# US_EPS_MCU.net
KiCad netlist of a schematic drawn in Altium Designer
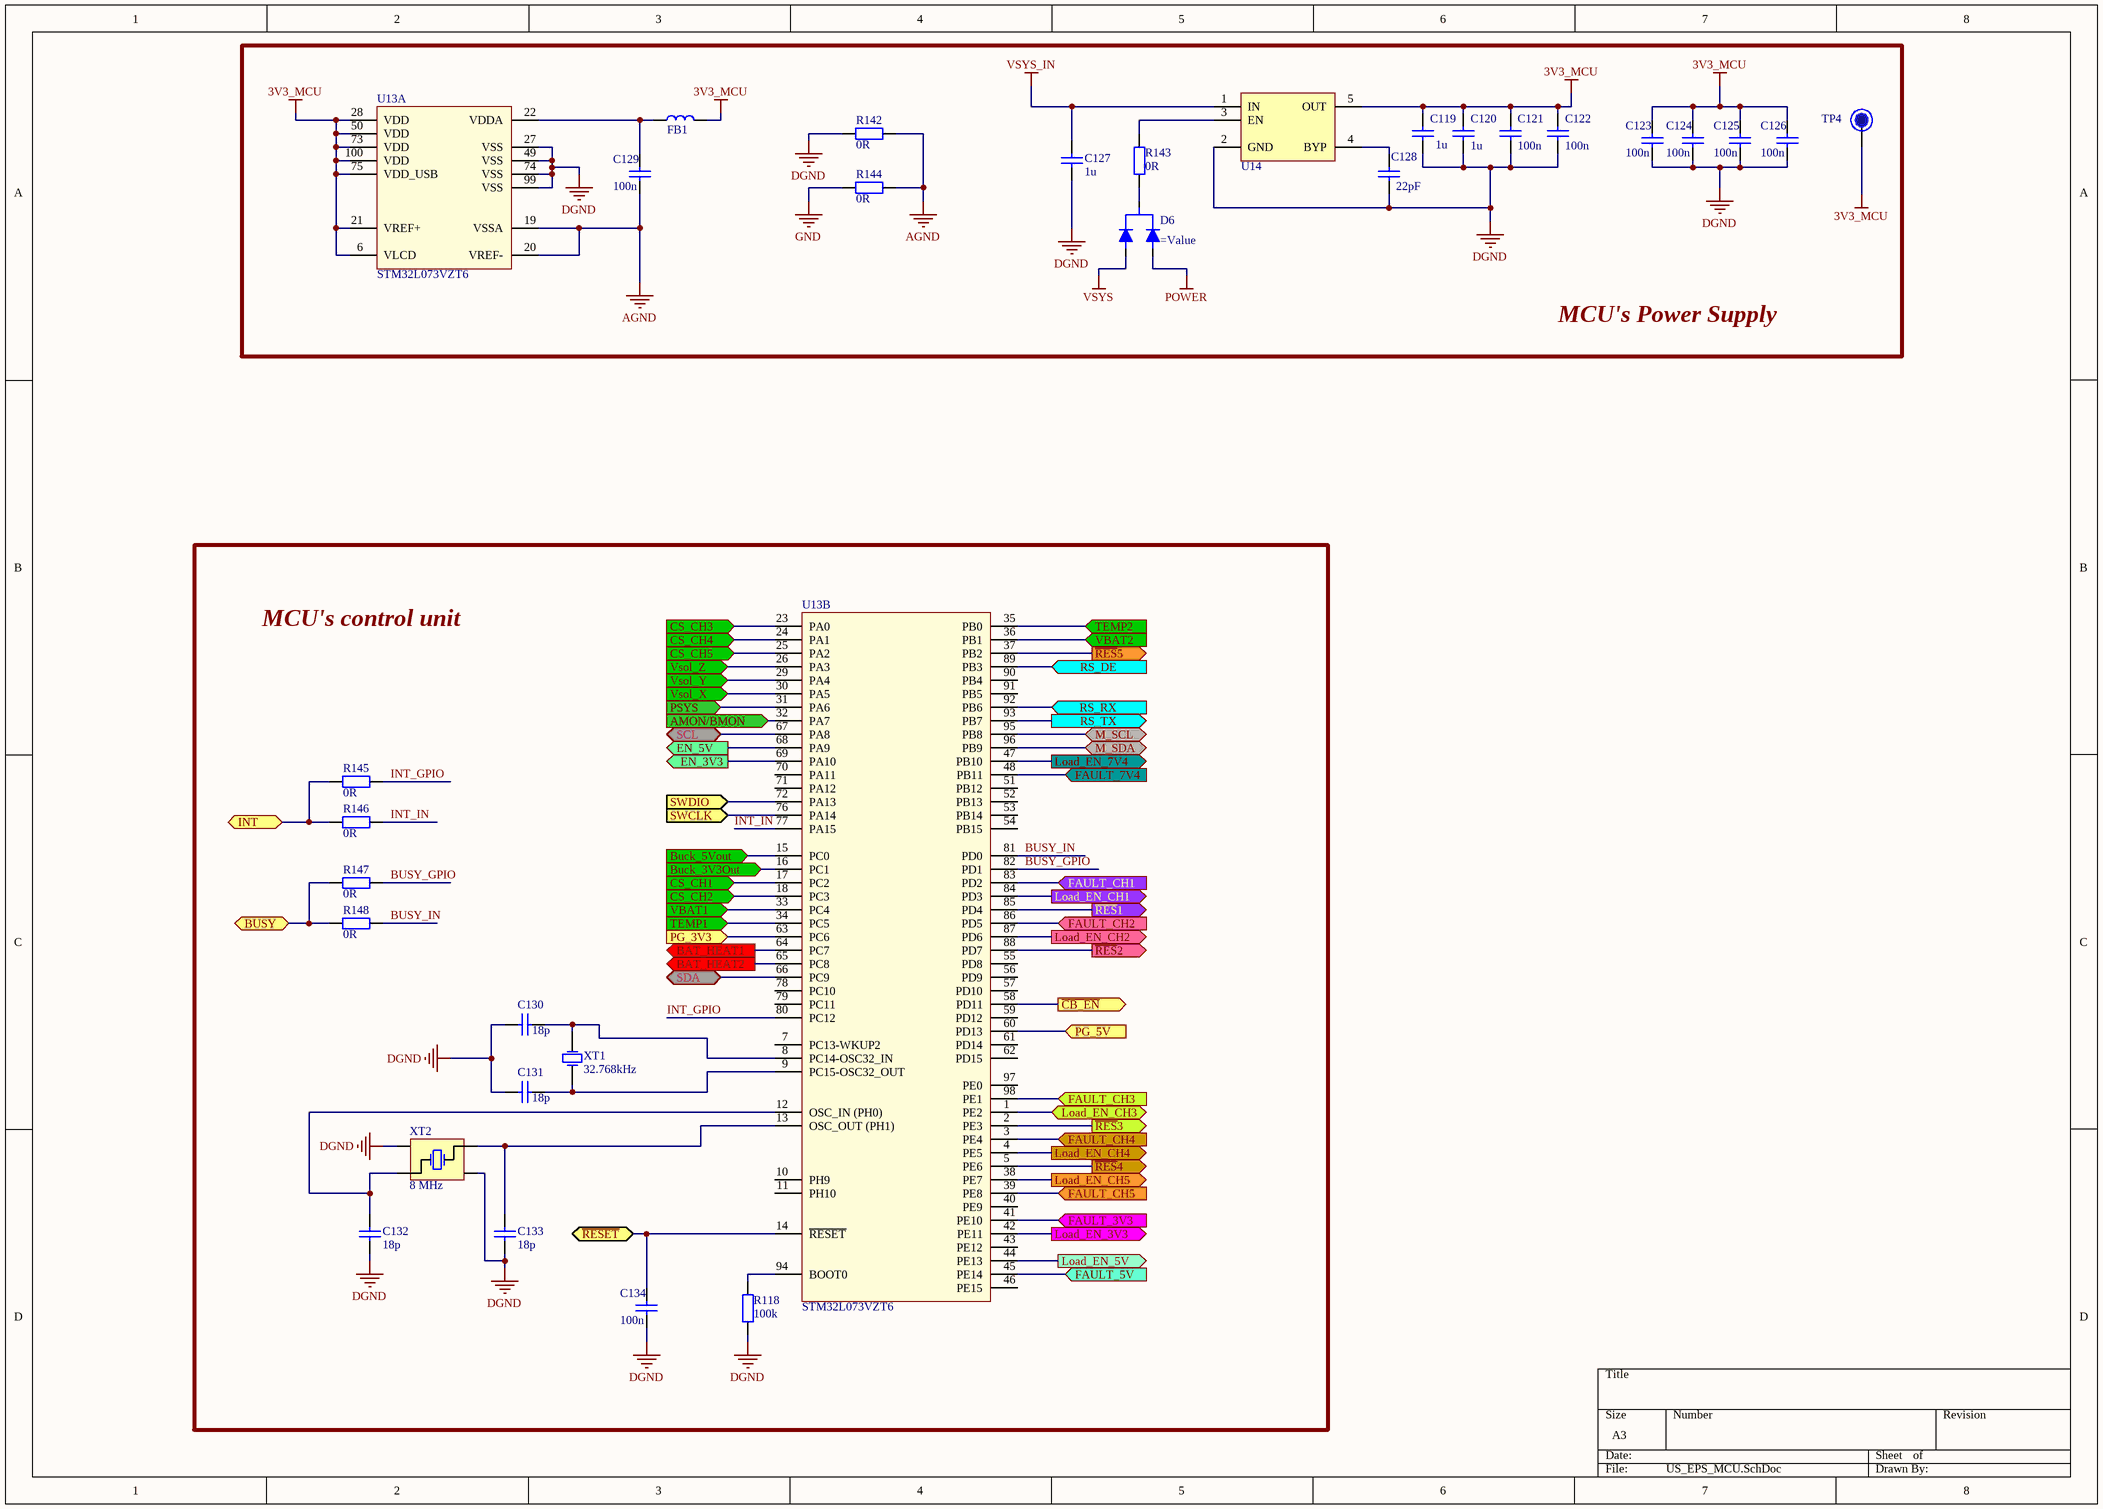
[diagram p0: US_EPS_MCU.SchDoc]

(export (version "E")
  (design (tool "Eeschema 10.0.6"))
  (components
    (comp (ref "C119")
      (value "1u")
      (footprint "C0603_IPC_HD")
      (description "CAP CER 1UF 16V X7R 0603")
      (fields
        (field (name "MANUFACTURER") "Samsung Electro-Mechanics")
        (field (name "MANUFACTURER PART NUMBER") "CL10B105MO8NNWC")
      )
      (libsource (lib "alfasat_lib") (part "CL10B105MO8NNWC"))
    )
    (comp (ref "C120")
      (value "1u")
      (footprint "C0603_IPC_HD")
      (description "CAP CER 1UF 16V X7R 0603")
      (fields
        (field (name "MANUFACTURER") "Samsung Electro-Mechanics")
        (field (name "MANUFACTURER PART NUMBER") "CL10B105MO8NNWC")
      )
      (libsource (lib "alfasat_lib") (part "CL10B105MO8NNWC"))
    )
    (comp (ref "C121")
      (value "100n")
      (footprint "C0603_IPC_HD")
      (description "CAP CER 0.1UF 16V X7R 0603")
      (fields
        (field (name "MANUFACTURER") "Samsung Electro-Mechanics")
        (field (name "MANUFACTURER PART NUMBER") "CL10B104KO8NNNC")
      )
      (libsource (lib "alfasat_lib") (part "CL10B104KO8NNNC"))
    )
    (comp (ref "C122")
      (value "100n")
      (footprint "C0603_IPC_HD")
      (description "CAP CER 0.1UF 16V X7R 0603")
      (fields
        (field (name "MANUFACTURER") "Samsung Electro-Mechanics")
        (field (name "MANUFACTURER PART NUMBER") "CL10B104KO8NNNC")
      )
      (libsource (lib "alfasat_lib") (part "CL10B104KO8NNNC"))
    )
    (comp (ref "C123")
      (value "100n")
      (footprint "C0603_IPC_HD")
      (description "CAP CER 0.1UF 16V X7R 0603")
      (fields
        (field (name "MANUFACTURER") "Samsung Electro-Mechanics")
        (field (name "MANUFACTURER PART NUMBER") "CL10B104KO8NNNC")
      )
      (libsource (lib "alfasat_lib") (part "CL10B104KO8NNNC"))
    )
    (comp (ref "C124")
      (value "100n")
      (footprint "C0603_IPC_HD")
      (description "CAP CER 0.1UF 16V X7R 0603")
      (fields
        (field (name "MANUFACTURER") "Samsung Electro-Mechanics")
        (field (name "MANUFACTURER PART NUMBER") "CL10B104KO8NNNC")
      )
      (libsource (lib "alfasat_lib") (part "CL10B104KO8NNNC"))
    )
    (comp (ref "C125")
      (value "100n")
      (footprint "C0603_IPC_HD")
      (description "CAP CER 0.1UF 16V X7R 0603")
      (fields
        (field (name "MANUFACTURER") "Samsung Electro-Mechanics")
        (field (name "MANUFACTURER PART NUMBER") "CL10B104KO8NNNC")
      )
      (libsource (lib "alfasat_lib") (part "CL10B104KO8NNNC"))
    )
    (comp (ref "C126")
      (value "100n")
      (footprint "C0603_IPC_HD")
      (description "CAP CER 0.1UF 16V X7R 0603")
      (fields
        (field (name "MANUFACTURER") "Samsung Electro-Mechanics")
        (field (name "MANUFACTURER PART NUMBER") "CL10B104KO8NNNC")
      )
      (libsource (lib "alfasat_lib") (part "CL10B104KO8NNNC"))
    )
    (comp (ref "C127")
      (value "1u")
      (footprint "C0603_IPC_HD")
      (description "CAP CER 1UF 16V X7R 0603")
      (fields
        (field (name "MANUFACTURER") "Samsung Electro-Mechanics")
        (field (name "MANUFACTURER PART NUMBER") "CL10B105MO8NNWC")
      )
      (libsource (lib "alfasat_lib") (part "CL10B105MO8NNWC"))
    )
    (comp (ref "C128")
      (value "22pF")
      (footprint "C0603_IPC_HD")
      (description "CAP CER 22PF 50V C0G/NP0 0603")
      (fields
        (field (name "MANUFACTURER") "Wurth Electronics Inc.")
        (field (name "MANUFACTURER PART NUMBER") "885012006053")
      )
      (libsource (lib "alfasat_lib_eps") (part "CL0603_22pF_50V"))
    )
    (comp (ref "C129")
      (value "100n")
      (footprint "C0603_IPC_HD")
      (description "CAP CER 0.1UF 16V X7R 0603")
      (fields
        (field (name "MANUFACTURER") "Samsung Electro-Mechanics")
        (field (name "MANUFACTURER PART NUMBER") "CL10B104KO8NNNC")
      )
      (libsource (lib "alfasat_lib") (part "CL10B104KO8NNNC"))
    )
    (comp (ref "C130")
      (value "18p")
      (footprint "C0603_IPC_HD")
      (description "CAP CER 18PF 50V C0G/NP0 0603")
      (fields
        (field (name "MANUFACTURER") "Samsung Electro-Mechanics")
        (field (name "MANUFACTURER PART NUMBER") "CL10C180JB8NNNC")
      )
      (libsource (lib "alfasat_lib") (part "CL10C180JB8NNNC"))
    )
    (comp (ref "C131")
      (value "18p")
      (footprint "C0603_IPC_HD")
      (description "CAP CER 18PF 50V C0G/NP0 0603")
      (fields
        (field (name "MANUFACTURER") "Samsung Electro-Mechanics")
        (field (name "MANUFACTURER PART NUMBER") "CL10C180JB8NNNC")
      )
      (libsource (lib "alfasat_lib") (part "CL10C180JB8NNNC"))
    )
    (comp (ref "C132")
      (value "18p")
      (footprint "C0603_IPC_HD")
      (description "CAP CER 18PF 50V C0G/NP0 0603")
      (fields
        (field (name "MANUFACTURER") "Samsung Electro-Mechanics")
        (field (name "MANUFACTURER PART NUMBER") "CL10C180JB8NNNC")
      )
      (libsource (lib "alfasat_lib") (part "CL10C180JB8NNNC"))
    )
    (comp (ref "C133")
      (value "18p")
      (footprint "C0603_IPC_HD")
      (description "CAP CER 18PF 50V C0G/NP0 0603")
      (fields
        (field (name "MANUFACTURER") "Samsung Electro-Mechanics")
        (field (name "MANUFACTURER PART NUMBER") "CL10C180JB8NNNC")
      )
      (libsource (lib "alfasat_lib") (part "CL10C180JB8NNNC"))
    )
    (comp (ref "C134")
      (value "100n")
      (footprint "C0603_IPC_HD")
      (description "CAP CER 0.1UF 16V X7R 0603")
      (fields
        (field (name "MANUFACTURER") "Samsung Electro-Mechanics")
        (field (name "MANUFACTURER PART NUMBER") "CL10B104KO8NNNC")
      )
      (libsource (lib "alfasat_lib") (part "CL10B104KO8NNNC"))
    )
    (comp (ref "D6")
      (value "~")
      (footprint "BAT54C_SOT23")
      (description "Diode Schottky 30V 200mA Surface Mount SOT-23(ISL9237)")
      (fields
        (field (name "MANUFACTURER") "Diodes Incorporated")
        (field (name "MANUFACTURER PART NUMBER") "BAT54CQ-7-F")
      )
      (libsource (lib "alfasat_lib_eps") (part "BAT54CQ-7"))
    )
    (comp (ref "FB1")
      (value "MH1608-601Y")
      (footprint "L0603_IPC_MD")
      (description "FERRITE BEAD 600R@100MHz 0603 for Power Line, 1000mA")
      (fields (field (name "MANUFACTURER") "Bourns Inc."))
      (libsource (lib "alfasat_lib") (part "MH1608-601Y"))
    )
    (comp (ref "R118")
      (value "100k")
      (footprint "R0603_IPC_MD")
      (description "RES 100K OHM 1% 1/10W 0603")
      (fields
        (field (name "MANUFACTURER") "Stackpole Electronics Inc")
        (field (name "MANUFACTURER PART NUMBER") "RMCF0603FT100K")
      )
      (libsource (lib "alfasat_lib_eps") (part "CR0603-JW-104ELF"))
    )
    (comp (ref "R142")
      (value "0R")
      (footprint "R0603_IPC_MD")
      (description "RES SMD 0 OHM JUMPER 1/10W 0603")
      (fields
        (field (name "MANUFACTURER") "Bourns Inc.")
        (field (name "MANUFACTURER PART NUMBER") "CR0603-J/-000ELF")
      )
      (libsource (lib "alfasat_lib") (part "CR0603-J/-000ELF"))
    )
    (comp (ref "R143")
      (value "0R")
      (footprint "R0603_IPC_MD")
      (description "RES SMD 0 OHM JUMPER 1/10W 0603")
      (fields
        (field (name "MANUFACTURER") "Bourns Inc.")
        (field (name "MANUFACTURER PART NUMBER") "CR0603-J/-000ELF")
      )
      (libsource (lib "") (part "CR0603-J/-000ELF_1"))
    )
    (comp (ref "R144")
      (value "0R")
      (footprint "R0603_IPC_MD")
      (description "RES SMD 0 OHM JUMPER 1/10W 0603")
      (fields
        (field (name "MANUFACTURER") "Bourns Inc.")
        (field (name "MANUFACTURER PART NUMBER") "CR0603-J/-000ELF")
      )
      (libsource (lib "alfasat_lib") (part "CR0603-J/-000ELF"))
    )
    (comp (ref "R145")
      (value "0R")
      (footprint "R0603_IPC_MD")
      (description "RES SMD 0 OHM JUMPER 1/10W 0603")
      (fields
        (field (name "MANUFACTURER") "Bourns Inc.")
        (field (name "MANUFACTURER PART NUMBER") "CR0603-J/-000ELF")
      )
      (libsource (lib "alfasat_lib") (part "CR0603-J/-000ELF"))
    )
    (comp (ref "R146")
      (value "0R")
      (footprint "R0603_IPC_MD")
      (description "RES SMD 0 OHM JUMPER 1/10W 0603")
      (fields
        (field (name "MANUFACTURER") "Bourns Inc.")
        (field (name "MANUFACTURER PART NUMBER") "CR0603-J/-000ELF")
      )
      (libsource (lib "alfasat_lib") (part "CR0603-J/-000ELF"))
    )
    (comp (ref "R147")
      (value "0R")
      (footprint "R0603_IPC_MD")
      (description "RES SMD 0 OHM JUMPER 1/10W 0603")
      (fields
        (field (name "MANUFACTURER") "Bourns Inc.")
        (field (name "MANUFACTURER PART NUMBER") "CR0603-J/-000ELF")
      )
      (libsource (lib "alfasat_lib") (part "CR0603-J/-000ELF"))
    )
    (comp (ref "R148")
      (value "0R")
      (footprint "R0603_IPC_MD")
      (description "RES SMD 0 OHM JUMPER 1/10W 0603")
      (fields
        (field (name "MANUFACTURER") "Bourns Inc.")
        (field (name "MANUFACTURER PART NUMBER") "CR0603-J/-000ELF")
      )
      (libsource (lib "alfasat_lib") (part "CR0603-J/-000ELF"))
    )
    (comp (ref "TP4")
      (value "Test Point")
      (footprint "TestPoint_1M5")
      (libsource (lib "alfasat_lib") (part "TP"))
    )
    (comp (ref "U13")
      (value "STM32L073VZT6")
      (footprint "STM32L073_TSQFP50P1600X1600X160-100N")
      (description "ARM® Cortex®-M0+ STM32L0 Microcontroller IC 32-Bit 32MHz 192KB (192K x 8) FLASH 100-LQFP (14x14)")
      (fields (field (name "MANUFACTURER") "STMicroelectronics"))
      (libsource (lib "alfasat_lib_eps") (part "STM32L073VZT6_EPS"))
    )
    (comp (ref "U14")
      (value "MIC5216-3.3YM5-TR")
      (footprint "SOT23-5_(MT)")
      (description "IC REG LINEAR 3.3V 500MA SOT23-5")
      (fields (field (name "MANUFACTURER") "Microchip Technology"))
      (libsource (lib "alfasat_lib_eps") (part "MIC5216-3.3YM5-TR"))
    )
    (comp (ref "XT1")
      (value "32.768kHz")
      (footprint "FC-135R")
      (description "32.768kHz ±20ppm Crystal 12.5pF 70 kOhms 2-SMD, No Lead")
      (fields
        (field (name "MANUFACTURER") "EPSON")
        (field (name "MANUFACTURER PART NUMBER") "FC-135 32.7680KA-A5")
      )
      (libsource (lib "alfasat_lib_eps") (part "FC-135-32.7680K"))
    )
    (comp (ref "XT2")
      (value "8 MHz")
      (footprint "5.0X3.2_4PAD_SMT")
      (description "8MHz ±10ppm Crystal 10pF 200 Ohms 4-SMD, No Lead")
      (fields
        (field (name "MANUFACTURER PART NUMBER") "ABM3B-8.000MHZ-10-1-U-T")
        (field (name "MANUFACTURER") "Abracon LLC")
      )
      (libsource (lib "alfasat_lib") (part "ABM3B-8.000MHZ-10-1-U-T"))
    )
  )
  (nets
    (net (code "1") (name "/AMON{slash}BMON") (class "Default")
      (node (ref "U13") (pin "32") (pinfunction "PA7_32") (pintype "passive"))
    )
    (net (code "2") (name "/BAT_HEAT1") (class "Default")
      (node (ref "U13") (pin "64") (pinfunction "PC7_64") (pintype "passive"))
    )
    (net (code "3") (name "/BAT_HEAT2") (class "Default")
      (node (ref "U13") (pin "65") (pinfunction "PC8_65") (pintype "passive"))
    )
    (net (code "4") (name "/BUSY") (class "Default")
      (node (ref "R147") (pin "2") (pinfunction "2_2") (pintype "passive"))
      (node (ref "R148") (pin "2") (pinfunction "2_2") (pintype "passive"))
    )
    (net (code "5") (name "/BUSY_GPIO") (class "Default")
      (node (ref "R147") (pin "1") (pinfunction "1_1") (pintype "passive"))
      (node (ref "U13") (pin "82") (pinfunction "PD1_82") (pintype "passive"))
    )
    (net (code "6") (name "/BUSY_IN") (class "Default")
      (node (ref "R148") (pin "1") (pinfunction "1_1") (pintype "passive"))
      (node (ref "U13") (pin "81") (pinfunction "PD0_81") (pintype "passive"))
    )
    (net (code "7") (name "/Buck_3V3Out") (class "Default")
      (node (ref "U13") (pin "16") (pinfunction "PC1_16") (pintype "passive"))
    )
    (net (code "8") (name "/Buck_5Vout") (class "Default")
      (node (ref "U13") (pin "15") (pinfunction "PC0_15") (pintype "passive"))
    )
    (net (code "9") (name "/CS_CH1") (class "Default")
      (node (ref "U13") (pin "17") (pinfunction "PC2_17") (pintype "passive"))
    )
    (net (code "10") (name "/CS_CH2") (class "Default")
      (node (ref "U13") (pin "18") (pinfunction "PC3_18") (pintype "passive"))
    )
    (net (code "11") (name "/CS_CH3") (class "Default")
      (node (ref "U13") (pin "23") (pinfunction "PA0_23") (pintype "passive"))
    )
    (net (code "12") (name "/CS_CH4") (class "Default")
      (node (ref "U13") (pin "24") (pinfunction "PA1_24") (pintype "passive"))
    )
    (net (code "13") (name "/CS_CH5") (class "Default")
      (node (ref "U13") (pin "25") (pinfunction "PA2_25") (pintype "passive"))
    )
    (net (code "14") (name "/EN_3V3") (class "Default")
      (node (ref "U13") (pin "69") (pinfunction "PA10_69") (pintype "passive"))
    )
    (net (code "15") (name "/EN_5V") (class "Default")
      (node (ref "U13") (pin "68") (pinfunction "PA9_68") (pintype "passive"))
    )
    (net (code "16") (name "/FAULT_3V3") (class "Default")
      (node (ref "U13") (pin "41") (pinfunction "PE10_41") (pintype "passive"))
    )
    (net (code "17") (name "/FAULT_5V") (class "Default")
      (node (ref "U13") (pin "45") (pinfunction "PE14_45") (pintype "passive"))
    )
    (net (code "18") (name "/FAULT_7V4") (class "Default")
      (node (ref "U13") (pin "48") (pinfunction "PB11_48") (pintype "passive"))
    )
    (net (code "19") (name "/FAULT_CH1") (class "Default")
      (node (ref "U13") (pin "83") (pinfunction "PD2_83") (pintype "passive"))
    )
    (net (code "20") (name "/FAULT_CH2") (class "Default")
      (node (ref "U13") (pin "86") (pinfunction "PD5_86") (pintype "passive"))
    )
    (net (code "21") (name "/FAULT_CH3") (class "Default")
      (node (ref "U13") (pin "98") (pinfunction "PE1_98") (pintype "passive"))
    )
    (net (code "22") (name "/FAULT_CH4") (class "Default")
      (node (ref "U13") (pin "3") (pinfunction "PE4_3") (pintype "passive"))
    )
    (net (code "23") (name "/FAULT_CH5") (class "Default")
      (node (ref "U13") (pin "39") (pinfunction "PE8_39") (pintype "passive"))
    )
    (net (code "24") (name "/INT") (class "Default")
      (node (ref "R145") (pin "2") (pinfunction "2_2") (pintype "passive"))
      (node (ref "R146") (pin "2") (pinfunction "2_2") (pintype "passive"))
    )
    (net (code "25") (name "/INT_GPIO") (class "Default")
      (node (ref "R145") (pin "1") (pinfunction "1_1") (pintype "passive"))
      (node (ref "U13") (pin "80") (pinfunction "PC12_80") (pintype "passive"))
    )
    (net (code "26") (name "/INT_IN") (class "Default")
      (node (ref "R146") (pin "1") (pinfunction "1_1") (pintype "passive"))
      (node (ref "U13") (pin "77") (pinfunction "PA15_77") (pintype "passive"))
    )
    (net (code "27") (name "/Load_EN_3V3") (class "Default")
      (node (ref "U13") (pin "42") (pinfunction "PE11_42") (pintype "passive"))
    )
    (net (code "28") (name "/Load_EN_5V") (class "Default")
      (node (ref "U13") (pin "44") (pinfunction "PE13_44") (pintype "passive"))
    )
    (net (code "29") (name "/Load_EN_7V4") (class "Default")
      (node (ref "U13") (pin "47") (pinfunction "PB10_47") (pintype "passive"))
    )
    (net (code "30") (name "/Load_EN_CH1") (class "Default")
      (node (ref "U13") (pin "84") (pinfunction "PD3_84") (pintype "passive"))
    )
    (net (code "31") (name "/Load_EN_CH2") (class "Default")
      (node (ref "U13") (pin "87") (pinfunction "PD6_87") (pintype "passive"))
    )
    (net (code "32") (name "/Load_EN_CH3") (class "Default")
      (node (ref "U13") (pin "1") (pinfunction "PE2_1") (pintype "power_in"))
    )
    (net (code "33") (name "/Load_EN_CH4") (class "Default")
      (node (ref "U13") (pin "4") (pinfunction "PE5_4") (pintype "passive"))
    )
    (net (code "34") (name "/Load_EN_CH5") (class "Default")
      (node (ref "U13") (pin "38") (pinfunction "PE7_38") (pintype "passive"))
    )
    (net (code "35") (name "/M_SCL") (class "Default")
      (node (ref "U13") (pin "95") (pinfunction "PB8_95") (pintype "passive"))
    )
    (net (code "36") (name "/M_SDA") (class "Default")
      (node (ref "U13") (pin "96") (pinfunction "PB9_96") (pintype "passive"))
    )
    (net (code "37") (name "/PG_3V3") (class "Default")
      (node (ref "U13") (pin "63") (pinfunction "PC6_63") (pintype "passive"))
    )
    (net (code "38") (name "/PG_5V") (class "Default")
      (node (ref "U13") (pin "60") (pinfunction "PD13_60") (pintype "passive"))
    )
    (net (code "39") (name "/PSYS") (class "Default")
      (node (ref "U13") (pin "31") (pinfunction "PA6_31") (pintype "passive"))
    )
    (net (code "40") (name "/RS_DE") (class "Default")
      (node (ref "U13") (pin "89") (pinfunction "PB3_89") (pintype "passive"))
    )
    (net (code "41") (name "/RS_RX") (class "Default")
      (node (ref "U13") (pin "92") (pinfunction "PB6_92") (pintype "passive"))
    )
    (net (code "42") (name "/RS_TX") (class "Default")
      (node (ref "U13") (pin "93") (pinfunction "PB7_93") (pintype "passive"))
    )
    (net (code "43") (name "/SCL") (class "Default")
      (node (ref "U13") (pin "67") (pinfunction "PA8_67") (pintype "passive"))
    )
    (net (code "44") (name "/SDA") (class "Default")
      (node (ref "U13") (pin "66") (pinfunction "PC9_66") (pintype "passive"))
    )
    (net (code "45") (name "/SWCLK") (class "Default")
      (node (ref "U13") (pin "76") (pinfunction "PA14_76") (pintype "passive"))
    )
    (net (code "46") (name "/SWDIO") (class "Default")
      (node (ref "U13") (pin "72") (pinfunction "PA13_72") (pintype "passive"))
    )
    (net (code "47") (name "/TEMP1") (class "Default")
      (node (ref "U13") (pin "34") (pinfunction "PC5_34") (pintype "passive"))
    )
    (net (code "48") (name "/TEMP2") (class "Default")
      (node (ref "U13") (pin "35") (pinfunction "PB0_35") (pintype "passive"))
    )
    (net (code "49") (name "/VBAT1") (class "Default")
      (node (ref "U13") (pin "33") (pinfunction "PC4_33") (pintype "passive"))
    )
    (net (code "50") (name "/VBAT2") (class "Default")
      (node (ref "U13") (pin "36") (pinfunction "PB1_36") (pintype "passive"))
    )
    (net (code "51") (name "/Vsol_X") (class "Default")
      (node (ref "U13") (pin "30") (pinfunction "PA5_30") (pintype "passive"))
    )
    (net (code "52") (name "/Vsol_Y") (class "Default")
      (node (ref "U13") (pin "29") (pinfunction "PA4_29") (pintype "passive"))
    )
    (net (code "53") (name "/Vsol_Z") (class "Default")
      (node (ref "U13") (pin "26") (pinfunction "PA3_26") (pintype "passive"))
    )
    (net (code "54") (name "/~{CB_EN}") (class "Default")
      (node (ref "U13") (pin "58") (pinfunction "PD11_58") (pintype "passive"))
    )
    (net (code "55") (name "/~{RESET}") (class "Default")
      (node (ref "C134") (pin "2") (pinfunction "2_2") (pintype "passive"))
      (node (ref "U13") (pin "14") (pinfunction "~{RESET}_14") (pintype "passive"))
    )
    (net (code "56") (name "/~{RES}1") (class "Default")
      (node (ref "U13") (pin "85") (pinfunction "PD4_85") (pintype "passive"))
    )
    (net (code "57") (name "/~{RES}2") (class "Default")
      (node (ref "U13") (pin "88") (pinfunction "PD7_88") (pintype "passive"))
    )
    (net (code "58") (name "/~{RES}3") (class "Default")
      (node (ref "U13") (pin "2") (pinfunction "PE3_2") (pintype "passive"))
    )
    (net (code "59") (name "/~{RES}4") (class "Default")
      (node (ref "U13") (pin "5") (pinfunction "PE6_5") (pintype "passive"))
    )
    (net (code "60") (name "/~{RES}5") (class "Default")
      (node (ref "U13") (pin "37") (pinfunction "PB2_37") (pintype "passive"))
    )
    (net (code "61") (name "3V3_MCU") (class "Default")
      (node (ref "C119") (pin "2") (pinfunction "2_2") (pintype "passive"))
      (node (ref "C120") (pin "2") (pinfunction "2_2") (pintype "passive"))
      (node (ref "C121") (pin "2") (pinfunction "2_2") (pintype "passive"))
      (node (ref "C122") (pin "2") (pinfunction "2_2") (pintype "passive"))
      (node (ref "C123") (pin "2") (pinfunction "2_2") (pintype "passive"))
      (node (ref "C124") (pin "2") (pinfunction "2_2") (pintype "passive"))
      (node (ref "C125") (pin "2") (pinfunction "2_2") (pintype "passive"))
      (node (ref "C126") (pin "2") (pinfunction "2_2") (pintype "passive"))
      (node (ref "FB1") (pin "2") (pinfunction "2_2") (pintype "passive"))
      (node (ref "TP4") (pin "0") (pinfunction "0_0") (pintype "passive"))
      (node (ref "U13") (pin "100") (pinfunction "VDD_100") (pintype "passive"))
      (node (ref "U13") (pin "21") (pinfunction "VREF+_21") (pintype "passive"))
      (node (ref "U13") (pin "28") (pinfunction "VDD_28") (pintype "passive"))
      (node (ref "U13") (pin "50") (pinfunction "VDD_50") (pintype "passive"))
      (node (ref "U13") (pin "6") (pinfunction "VLCD_6") (pintype "passive"))
      (node (ref "U13") (pin "73") (pinfunction "VDD_73") (pintype "passive"))
      (node (ref "U13") (pin "75") (pinfunction "VDD_USB_75") (pintype "passive"))
      (node (ref "U14") (pin "5") (pinfunction "OUT_5") (pintype "passive"))
    )
    (net (code "62") (name "AGND") (class "Default")
      (node (ref "C129") (pin "1") (pinfunction "1_1") (pintype "passive"))
      (node (ref "R142") (pin "1") (pinfunction "1_1") (pintype "passive"))
      (node (ref "R144") (pin "1") (pinfunction "1_1") (pintype "passive"))
      (node (ref "U13") (pin "19") (pinfunction "VSSA_19") (pintype "passive"))
      (node (ref "U13") (pin "20") (pinfunction "VREF-_20") (pintype "passive"))
    )
    (net (code "63") (name "DGND") (class "Default")
      (node (ref "C119") (pin "1") (pinfunction "1_1") (pintype "passive"))
      (node (ref "C120") (pin "1") (pinfunction "1_1") (pintype "passive"))
      (node (ref "C121") (pin "1") (pinfunction "1_1") (pintype "passive"))
      (node (ref "C122") (pin "1") (pinfunction "1_1") (pintype "passive"))
      (node (ref "C123") (pin "1") (pinfunction "1_1") (pintype "passive"))
      (node (ref "C124") (pin "1") (pinfunction "1_1") (pintype "passive"))
      (node (ref "C125") (pin "1") (pinfunction "1_1") (pintype "passive"))
      (node (ref "C126") (pin "1") (pinfunction "1_1") (pintype "passive"))
      (node (ref "C127") (pin "1") (pinfunction "1_1") (pintype "passive"))
      (node (ref "C128") (pin "1") (pinfunction "1_1") (pintype "passive"))
      (node (ref "C130") (pin "1") (pinfunction "1_1") (pintype "passive"))
      (node (ref "C131") (pin "1") (pinfunction "1_1") (pintype "passive"))
      (node (ref "C132") (pin "1") (pinfunction "1_1") (pintype "passive"))
      (node (ref "C133") (pin "1") (pinfunction "1_1") (pintype "passive"))
      (node (ref "C134") (pin "1") (pinfunction "1_1") (pintype "passive"))
      (node (ref "R118") (pin "1") (pinfunction "1_1") (pintype "passive"))
      (node (ref "R142") (pin "2") (pinfunction "2_2") (pintype "passive"))
      (node (ref "U13") (pin "27") (pinfunction "VSS_27") (pintype "passive"))
      (node (ref "U13") (pin "49") (pinfunction "VSS_49") (pintype "passive"))
      (node (ref "U13") (pin "74") (pinfunction "VSS_74") (pintype "passive"))
      (node (ref "U13") (pin "99") (pinfunction "VSS_99") (pintype "passive"))
      (node (ref "U14") (pin "2") (pinfunction "GND_2") (pintype "passive"))
      (node (ref "XT2") (pin "2") (pinfunction "NC_2") (pintype "passive"))
      (node (ref "XT2") (pin "4") (pinfunction "NC_4") (pintype "passive"))
    )
    (net (code "64") (name "GND") (class "Default")
      (node (ref "R144") (pin "2") (pinfunction "2_2") (pintype "passive"))
    )
    (net (code "65") (name "Net-(D6-Pad3)") (class "Default")
      (node (ref "D6") (pin "3") (pinfunction "3_3") (pintype "passive"))
      (node (ref "R143") (pin "1") (pinfunction "1_1") (pintype "passive"))
    )
    (net (code "66") (name "Net-(U13A-VDDA)") (class "Default")
      (node (ref "C129") (pin "2") (pinfunction "2_2") (pintype "passive"))
      (node (ref "FB1") (pin "1") (pinfunction "1_1") (pintype "passive"))
      (node (ref "U13") (pin "22") (pinfunction "VDDA_22") (pintype "passive"))
    )
    (net (code "67") (name "Net-(U13B-BOOT0)") (class "Default")
      (node (ref "R118") (pin "2") (pinfunction "2_2") (pintype "passive"))
      (node (ref "U13") (pin "94") (pinfunction "BOOT0_94") (pintype "passive"))
    )
    (net (code "68") (name "Net-(U13B-OSC_IN_(PH0))") (class "Default")
      (node (ref "C132") (pin "2") (pinfunction "2_2") (pintype "passive"))
      (node (ref "U13") (pin "12") (pinfunction "OSC_IN_(PH0)_12") (pintype "passive"))
      (node (ref "XT2") (pin "3") (pinfunction "OSC2_3") (pintype "passive"))
    )
    (net (code "69") (name "Net-(U13B-OSC_OUT_(PH1))") (class "Default")
      (node (ref "C133") (pin "2") (pinfunction "2_2") (pintype "passive"))
      (node (ref "U13") (pin "13") (pinfunction "OSC_OUT_(PH1)_13") (pintype "passive"))
      (node (ref "XT2") (pin "1") (pinfunction "OSC1_1") (pintype "passive"))
    )
    (net (code "70") (name "Net-(U13B-PC14-OSC32_IN)") (class "Default")
      (node (ref "C130") (pin "2") (pinfunction "2_2") (pintype "passive"))
      (node (ref "U13") (pin "8") (pinfunction "PC14-OSC32_IN_8") (pintype "passive"))
      (node (ref "XT1") (pin "2") (pinfunction "OSC2_2") (pintype "passive"))
    )
    (net (code "71") (name "Net-(U13B-PC15-OSC32_OUT)") (class "Default")
      (node (ref "C131") (pin "2") (pinfunction "2_2") (pintype "passive"))
      (node (ref "U13") (pin "9") (pinfunction "PC15-OSC32_OUT_9") (pintype "passive"))
      (node (ref "XT1") (pin "1") (pinfunction "OSC1_1") (pintype "passive"))
    )
    (net (code "72") (name "Net-(U14-BYP)") (class "Default")
      (node (ref "C128") (pin "2") (pinfunction "2_2") (pintype "passive"))
      (node (ref "U14") (pin "4") (pinfunction "BYP_4") (pintype "passive"))
    )
    (net (code "73") (name "Net-(U14-EN)") (class "Default")
      (node (ref "R143") (pin "2") (pinfunction "2_2") (pintype "passive"))
      (node (ref "U14") (pin "3") (pinfunction "EN_3") (pintype "passive"))
    )
    (net (code "74") (name "POWER") (class "Default")
      (node (ref "D6") (pin "2") (pinfunction "2_2") (pintype "passive"))
    )
    (net (code "75") (name "VSYS") (class "Default")
      (node (ref "D6") (pin "1") (pinfunction "1_1") (pintype "passive"))
    )
    (net (code "76") (name "VSYS_IN") (class "Default")
      (node (ref "C127") (pin "2") (pinfunction "2_2") (pintype "passive"))
      (node (ref "U14") (pin "1") (pinfunction "IN_1") (pintype "passive"))
    )
    (net (code "77") (name "unconnected-(U13B-PA11-Pad70)") (class "Default")
      (node (ref "U13") (pin "70") (pinfunction "PA11_70") (pintype "passive"))
    )
    (net (code "78") (name "unconnected-(U13B-PA12-Pad71)") (class "Default")
      (node (ref "U13") (pin "71") (pinfunction "PA12_71") (pintype "passive"))
    )
    (net (code "79") (name "unconnected-(U13B-PB4-Pad90)") (class "Default")
      (node (ref "U13") (pin "90") (pinfunction "PB4_90") (pintype "passive"))
    )
    (net (code "80") (name "unconnected-(U13B-PB5-Pad91)") (class "Default")
      (node (ref "U13") (pin "91") (pinfunction "PB5_91") (pintype "passive"))
    )
    (net (code "81") (name "unconnected-(U13B-PB12-Pad51)") (class "Default")
      (node (ref "U13") (pin "51") (pinfunction "PB12_51") (pintype "passive"))
    )
    (net (code "82") (name "unconnected-(U13B-PB13-Pad52)") (class "Default")
      (node (ref "U13") (pin "52") (pinfunction "PB13_52") (pintype "passive"))
    )
    (net (code "83") (name "unconnected-(U13B-PB14-Pad53)") (class "Default")
      (node (ref "U13") (pin "53") (pinfunction "PB14_53") (pintype "passive"))
    )
    (net (code "84") (name "unconnected-(U13B-PB15-Pad54)") (class "Default")
      (node (ref "U13") (pin "54") (pinfunction "PB15_54") (pintype "passive"))
    )
    (net (code "85") (name "unconnected-(U13B-PC10-Pad78)") (class "Default")
      (node (ref "U13") (pin "78") (pinfunction "PC10_78") (pintype "passive"))
    )
    (net (code "86") (name "unconnected-(U13B-PC11-Pad79)") (class "Default")
      (node (ref "U13") (pin "79") (pinfunction "PC11_79") (pintype "passive"))
    )
    (net (code "87") (name "unconnected-(U13B-PC13-WKUP2-Pad7)") (class "Default")
      (node (ref "U13") (pin "7") (pinfunction "PC13-WKUP2_7") (pintype "passive"))
    )
    (net (code "88") (name "unconnected-(U13B-PD8-Pad55)") (class "Default")
      (node (ref "U13") (pin "55") (pinfunction "PD8_55") (pintype "passive"))
    )
    (net (code "89") (name "unconnected-(U13B-PD9-Pad56)") (class "Default")
      (node (ref "U13") (pin "56") (pinfunction "PD9_56") (pintype "passive"))
    )
    (net (code "90") (name "unconnected-(U13B-PD10-Pad57)") (class "Default")
      (node (ref "U13") (pin "57") (pinfunction "PD10_57") (pintype "passive"))
    )
    (net (code "91") (name "unconnected-(U13B-PD12-Pad59)") (class "Default")
      (node (ref "U13") (pin "59") (pinfunction "PD12_59") (pintype "passive"))
    )
    (net (code "92") (name "unconnected-(U13B-PD14-Pad61)") (class "Default")
      (node (ref "U13") (pin "61") (pinfunction "PD14_61") (pintype "passive"))
    )
    (net (code "93") (name "unconnected-(U13B-PD15-Pad62)") (class "Default")
      (node (ref "U13") (pin "62") (pinfunction "PD15_62") (pintype "passive"))
    )
    (net (code "94") (name "unconnected-(U13B-PE0-Pad97)") (class "Default")
      (node (ref "U13") (pin "97") (pinfunction "PE0_97") (pintype "passive"))
    )
    (net (code "95") (name "unconnected-(U13B-PE9-Pad40)") (class "Default")
      (node (ref "U13") (pin "40") (pinfunction "PE9_40") (pintype "passive"))
    )
    (net (code "96") (name "unconnected-(U13B-PE12-Pad43)") (class "Default")
      (node (ref "U13") (pin "43") (pinfunction "PE12_43") (pintype "passive"))
    )
    (net (code "97") (name "unconnected-(U13B-PE15-Pad46)") (class "Default")
      (node (ref "U13") (pin "46") (pinfunction "PE15_46") (pintype "passive"))
    )
    (net (code "98") (name "unconnected-(U13B-PH9-Pad10)") (class "Default")
      (node (ref "U13") (pin "10") (pinfunction "PH9_10") (pintype "passive"))
    )
    (net (code "99") (name "unconnected-(U13B-PH10-Pad11)") (class "Default")
      (node (ref "U13") (pin "11") (pinfunction "PH10_11") (pintype "passive"))
    )
  )
)
